# Main.net
KiCad netlist of a schematic drawn in Altium Designer
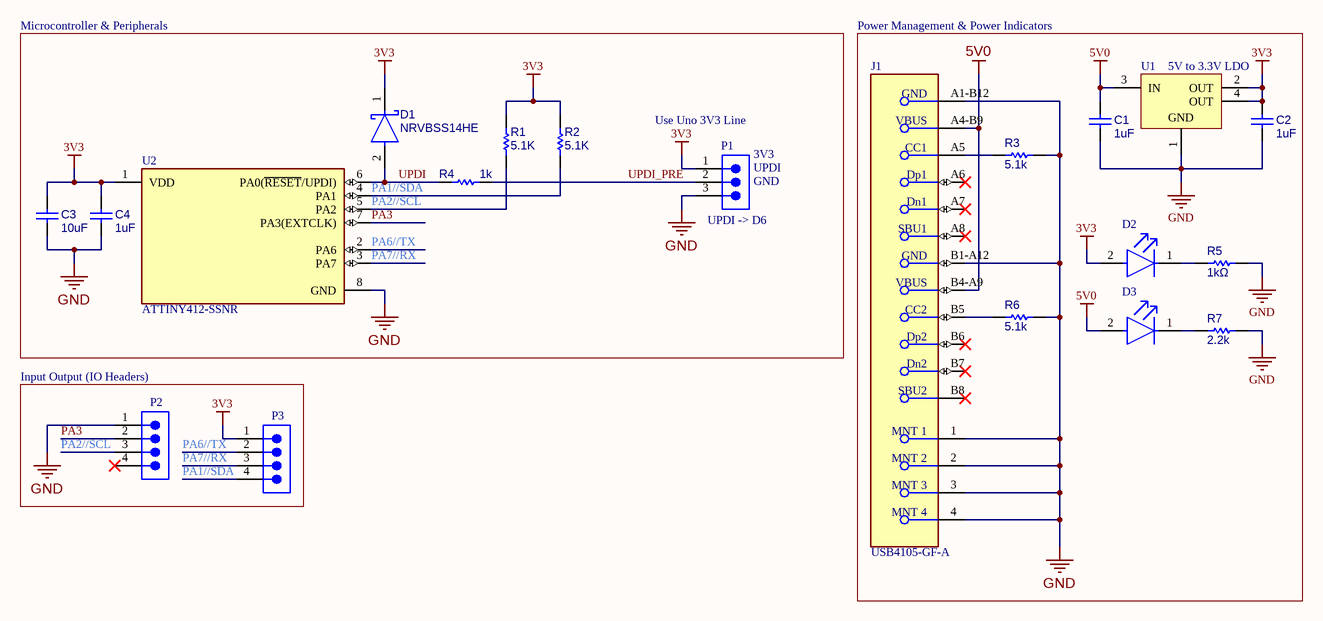
[diagram p0: Main.SchDoc]

(export (version "E")
  (design (tool "Eeschema 10.0.6"))
  (components
    (comp (ref "C1")
      (value "1uF")
      (footprint "WCAP-CSGP_0603_L1.6W0.8H0.8_Reflow")
      (description "10V tolerance")
      (libsource (lib "Altium Content Vault") (part "Capacitor_Non-Polarized"))
    )
    (comp (ref "C2")
      (value "1uF")
      (footprint "WCAP-CSGP_0603_L1.6W0.8H0.8_Reflow")
      (description "10V tolerance")
      (libsource (lib "Altium Content Vault") (part "Capacitor_Non-Polarized"))
    )
    (comp (ref "C3")
      (value "10uF")
      (footprint "WCAP-CSGP_0603_L1.6W0.8H0.8_Reflow")
      (description "10V tolerance")
      (libsource (lib "Altium Content Vault") (part "Capacitor_Non-Polarized"))
    )
    (comp (ref "C4")
      (value "1uF")
      (footprint "WCAP-CSGP_0603_L1.6W0.8H0.8_Reflow")
      (description "10V tolerance")
      (libsource (lib "Altium Content Vault") (part "Capacitor_Non-Polarized"))
    )
    (comp (ref "D1")
      (value "NRVBSS14HE")
      (footprint "FP-477AD-MFG")
      (description "NRVBSS14HE Rectifier Diode, Schottky, 1 Phase, 1 Element, 1A, 40V V(RRM), Silicon")
      (libsource (lib "Altium Content Vault") (part "c1678fac7984e62e0809fbf79c06691"))
    )
    (comp (ref "D2")
      (value "LTST-C190KGKT")
      (footprint "FP-LTST-C190KGKT-MFG")
      (description "LED GREEN CLEAR CHIP SMD")
      (libsource (lib "Altium Content Vault") (part "8706943c75ba83719d021d2fdc84c58"))
    )
    (comp (ref "D3")
      (value "LTST-C190KGKT")
      (footprint "FP-LTST-C190KGKT-MFG")
      (description "LED GREEN CLEAR CHIP SMD")
      (libsource (lib "Altium Content Vault") (part "8706943c75ba83719d021d2fdc84c58"))
    )
    (comp (ref "J1")
      (value "USB4105-GF-A")
      (footprint "FP-USB4105-GF-A-MFG")
      (description "CONN RCPT USB2.0 TYPEC 5A")
      (fields
        (field (name "MANUFACTURER") "GCT")
        (field (name "OCTOPART") "https://octopart.com/usb4105-gf-a-gct-106627878")
      )
      (libsource (lib "Altium Content Vault") (part "e7c17a616881a82b79941196b4bec10"))
    )
    (comp (ref "P1")
      (value "61300311121")
      (footprint "61300311121")
      (libsource (lib "Altium Content Vault") (part "Header_Male_1R_03P"))
    )
    (comp (ref "P2")
      (value "61300411121")
      (footprint "61300411121")
      (libsource (lib "Altium Content Vault") (part "Header_Male_1R_04P"))
    )
    (comp (ref "P3")
      (value "61300411121")
      (footprint "61300411121")
      (libsource (lib "Altium Content Vault") (part "Header_Male_1R_04P"))
    )
    (comp (ref "R1")
      (value "5.1K")
      (footprint "RESC1608X55X25NL10T15")
      (libsource (lib "Altium Content Vault") (part "RES"))
    )
    (comp (ref "R2")
      (value "5.1K")
      (footprint "RESC1608X55X25NL10T15")
      (libsource (lib "Altium Content Vault") (part "RES"))
    )
    (comp (ref "R3")
      (value "5.1k")
      (footprint "RESC1608X55X25NL10T15")
      (libsource (lib "Altium Content Vault") (part "RES"))
    )
    (comp (ref "R4")
      (value "1k")
      (footprint "RESC1608X55X25NL10T15")
      (libsource (lib "Altium Content Vault") (part "RES"))
    )
    (comp (ref "R5")
      (value "1kΩ")
      (footprint "RESC1608X55X25NL10T15")
      (libsource (lib "Altium Content Vault") (part "RES"))
    )
    (comp (ref "R6")
      (value "5.1k")
      (footprint "RESC1608X55X25NL10T15")
      (libsource (lib "Altium Content Vault") (part "RES"))
    )
    (comp (ref "R7")
      (value "2.2k")
      (footprint "RESC1608X55X25NL10T15")
      (libsource (lib "Altium Content Vault") (part "RES"))
    )
    (comp (ref "U1")
      (value "TLV1117LV33DCYR")
      (footprint "DCY0004A_N")
      (fields (field (name "MANUFACTURER") "Texas Instruments"))
      (libsource (lib "Altium Content Vault") (part "TI-TLV1117LV33DCY4"))
    )
    (comp (ref "U2")
      (value "ATTINY412-SSNR")
      (footprint "FP-C04-057-SN-MFG")
      (description "IC MCU 8BIT 4KB FLASH 8SOIC")
      (libsource (lib "Altium Content Vault") (part "d4679a08d650c91aafeef34e1c56fd9"))
    )
  )
  (nets
    (net (code "1") (name "/PA1{slash}{slash}SDA") (class "Default")
      (node (ref "P3") (pin "4") (pinfunction "4_4") (pintype "passive"))
      (node (ref "R2") (pin "2") (pinfunction "2_2") (pintype "passive"))
      (node (ref "U2") (pin "4") (pinfunction "PA1_4") (pintype "bidirectional"))
    )
    (net (code "2") (name "/PA2{slash}{slash}SCL") (class "Default")
      (node (ref "P2") (pin "3") (pinfunction "3_3") (pintype "passive"))
      (node (ref "R1") (pin "2") (pinfunction "2_2") (pintype "passive"))
      (node (ref "U2") (pin "5") (pinfunction "PA2_5") (pintype "bidirectional"))
    )
    (net (code "3") (name "/PA3") (class "Default")
      (node (ref "P2") (pin "2") (pinfunction "2_2") (pintype "passive"))
      (node (ref "U2") (pin "7") (pinfunction "PA3(EXTCLK)_7") (pintype "bidirectional"))
    )
    (net (code "4") (name "/PA6{slash}{slash}TX") (class "Default")
      (node (ref "P3") (pin "2") (pinfunction "2_2") (pintype "passive"))
      (node (ref "U2") (pin "2") (pinfunction "PA6_2") (pintype "bidirectional"))
    )
    (net (code "5") (name "/PA7{slash}{slash}RX") (class "Default")
      (node (ref "P3") (pin "3") (pinfunction "3_3") (pintype "passive"))
      (node (ref "U2") (pin "3") (pinfunction "PA7_3") (pintype "bidirectional"))
    )
    (net (code "6") (name "/UPDI") (class "Default")
      (node (ref "D1") (pin "2") (pinfunction "A_2") (pintype "passive"))
      (node (ref "R4") (pin "2") (pinfunction "2_2") (pintype "passive"))
      (node (ref "U2") (pin "6") (pinfunction "PA0(~{RESET}/UPDI)_6") (pintype "bidirectional"))
    )
    (net (code "7") (name "/UPDI_PRE") (class "Default")
      (node (ref "P1") (pin "2") (pinfunction "2_2") (pintype "passive"))
      (node (ref "R4") (pin "1") (pinfunction "1_1") (pintype "passive"))
    )
    (net (code "8") (name "3V3") (class "Default")
      (node (ref "C2") (pin "2") (pinfunction "2_2") (pintype "passive"))
      (node (ref "C3") (pin "2") (pinfunction "2_2") (pintype "passive"))
      (node (ref "C4") (pin "2") (pinfunction "2_2") (pintype "passive"))
      (node (ref "D1") (pin "1") (pinfunction "C_1") (pintype "passive"))
      (node (ref "D2") (pin "2") (pinfunction "A_2") (pintype "passive"))
      (node (ref "P1") (pin "1") (pinfunction "1_1") (pintype "passive"))
      (node (ref "P3") (pin "1") (pinfunction "1_1") (pintype "passive"))
      (node (ref "R1") (pin "1") (pinfunction "1_1") (pintype "passive"))
      (node (ref "R2") (pin "1") (pinfunction "1_1") (pintype "passive"))
      (node (ref "U1") (pin "2") (pinfunction "OUT_2") (pintype "power_in"))
      (node (ref "U1") (pin "4") (pinfunction "OUT_4") (pintype "power_in"))
      (node (ref "U2") (pin "1") (pinfunction "VDD_1") (pintype "power_in"))
    )
    (net (code "9") (name "5V0") (class "Default")
      (node (ref "C1") (pin "2") (pinfunction "2_2") (pintype "passive"))
      (node (ref "D3") (pin "2") (pinfunction "A_2") (pintype "passive"))
      (node (ref "J1") (pin "A4-B9") (pinfunction "VBUS_A4-B9") (pintype "power_in"))
      (node (ref "J1") (pin "B4-A9") (pinfunction "VBUS_B4-A9") (pintype "bidirectional"))
      (node (ref "U1") (pin "3") (pinfunction "IN_3") (pintype "power_in"))
    )
    (net (code "10") (name "GND") (class "Default")
      (node (ref "C1") (pin "1") (pinfunction "1_1") (pintype "passive"))
      (node (ref "C2") (pin "1") (pinfunction "1_1") (pintype "passive"))
      (node (ref "C3") (pin "1") (pinfunction "1_1") (pintype "passive"))
      (node (ref "C4") (pin "1") (pinfunction "1_1") (pintype "passive"))
      (node (ref "J1") (pin "1") (pinfunction "MNT_1_1") (pintype "power_in"))
      (node (ref "J1") (pin "2") (pinfunction "MNT_2_2") (pintype "power_in"))
      (node (ref "J1") (pin "3") (pinfunction "MNT_3_3") (pintype "power_in"))
      (node (ref "J1") (pin "4") (pinfunction "MNT_4_4") (pintype "power_in"))
      (node (ref "J1") (pin "A1-B12") (pinfunction "GND_A1-B12") (pintype "power_in"))
      (node (ref "J1") (pin "B1-A12") (pinfunction "GND_B1-A12") (pintype "bidirectional"))
      (node (ref "P1") (pin "3") (pinfunction "3_3") (pintype "passive"))
      (node (ref "P2") (pin "1") (pinfunction "1_1") (pintype "passive"))
      (node (ref "R3") (pin "1") (pinfunction "1_1") (pintype "passive"))
      (node (ref "R5") (pin "1") (pinfunction "1_1") (pintype "passive"))
      (node (ref "R6") (pin "1") (pinfunction "1_1") (pintype "passive"))
      (node (ref "R7") (pin "1") (pinfunction "1_1") (pintype "passive"))
      (node (ref "U1") (pin "1") (pinfunction "GND_1") (pintype "power_in"))
      (node (ref "U2") (pin "8") (pinfunction "GND_8") (pintype "power_in"))
    )
    (net (code "11") (name "Net-(D2-C)") (class "Default")
      (node (ref "D2") (pin "1") (pinfunction "C_1") (pintype "passive"))
      (node (ref "R5") (pin "2") (pinfunction "2_2") (pintype "passive"))
    )
    (net (code "12") (name "Net-(D3-C)") (class "Default")
      (node (ref "D3") (pin "1") (pinfunction "C_1") (pintype "passive"))
      (node (ref "R7") (pin "2") (pinfunction "2_2") (pintype "passive"))
    )
    (net (code "13") (name "Net-(J1-CC1)") (class "Default")
      (node (ref "J1") (pin "A5") (pinfunction "CC1_A5") (pintype "power_in"))
      (node (ref "R3") (pin "2") (pinfunction "2_2") (pintype "passive"))
    )
    (net (code "14") (name "Net-(J1-CC2)") (class "Default")
      (node (ref "J1") (pin "B5") (pinfunction "CC2_B5") (pintype "bidirectional"))
      (node (ref "R6") (pin "2") (pinfunction "2_2") (pintype "passive"))
    )
    (net (code "15") (name "unconnected-(J1-Dn1-PadA7)") (class "Default")
      (node (ref "J1") (pin "A7") (pinfunction "Dn1_A7") (pintype "bidirectional+no_connect"))
    )
    (net (code "16") (name "unconnected-(J1-Dn2-PadB7)") (class "Default")
      (node (ref "J1") (pin "B7") (pinfunction "Dn2_B7") (pintype "bidirectional+no_connect"))
    )
    (net (code "17") (name "unconnected-(J1-Dp1-PadA6)") (class "Default")
      (node (ref "J1") (pin "A6") (pinfunction "Dp1_A6") (pintype "bidirectional+no_connect"))
    )
    (net (code "18") (name "unconnected-(J1-Dp2-PadB6)") (class "Default")
      (node (ref "J1") (pin "B6") (pinfunction "Dp2_B6") (pintype "bidirectional+no_connect"))
    )
    (net (code "19") (name "unconnected-(J1-SBU1-PadA8)") (class "Default")
      (node (ref "J1") (pin "A8") (pinfunction "SBU1_A8") (pintype "bidirectional+no_connect"))
    )
    (net (code "20") (name "unconnected-(J1-SBU2-PadB8)") (class "Default")
      (node (ref "J1") (pin "B8") (pinfunction "SBU2_B8") (pintype "power_in+no_connect"))
    )
    (net (code "21") (name "unconnected-(P2-Pad4)") (class "Default")
      (node (ref "P2") (pin "4") (pinfunction "4_4") (pintype "passive+no_connect"))
    )
  )
)
